# SelfTestWiring.net
KiCad netlist of a schematic drawn in EAGLE
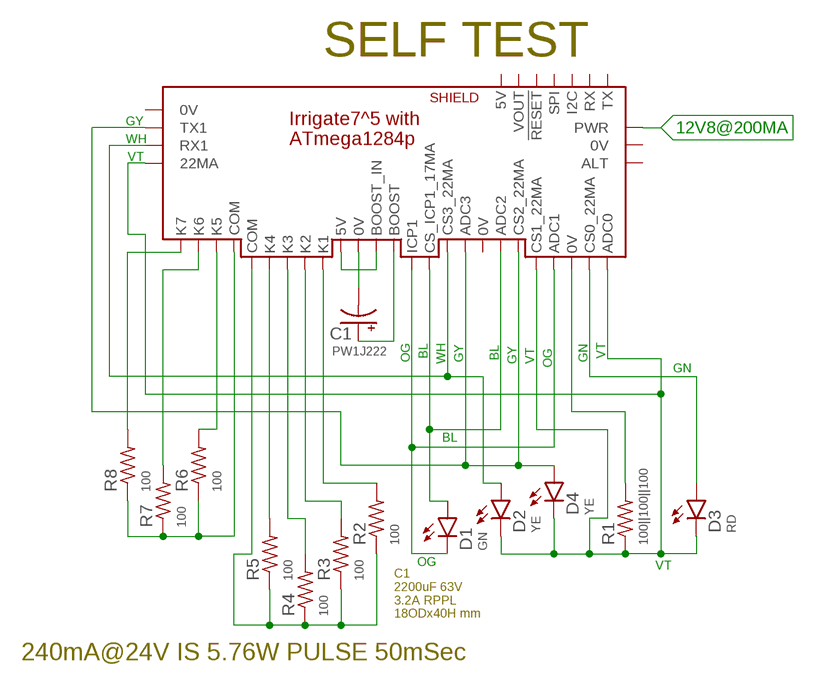
[diagram p0: schematic, sheet 1]

(export (version "E")
  (design (tool "Eeschema 10.0.6"))
  (components
    (comp (ref "C1")
      (value "PW1J222")
      (footprint "eagle-import:E7,5-18")
      (libsource (lib "eagle-import") (part "C-AL7.5X18"))
    )
    (comp (ref "D1")
      (value "GN")
      (footprint "eagle-import:LED5MM")
      (libsource (lib "eagle-import") (part "LED5MM"))
    )
    (comp (ref "D2")
      (value "YE")
      (footprint "eagle-import:LED5MM")
      (libsource (lib "eagle-import") (part "LED5MM"))
    )
    (comp (ref "D3")
      (value "RD")
      (footprint "eagle-import:LED5MM")
      (libsource (lib "eagle-import") (part "LED5MM"))
    )
    (comp (ref "D4")
      (value "YE")
      (footprint "eagle-import:LED5MM")
      (libsource (lib "eagle-import") (part "LED5MM"))
    )
    (comp (ref "R1")
      (value "100||100||100")
      (footprint "eagle-import:C0805(2012)")
      (libsource (lib "eagle-import") (part "R0805"))
    )
    (comp (ref "R2")
      (value "100")
      (footprint "eagle-import:C0805(2012)")
      (libsource (lib "eagle-import") (part "R0805"))
    )
    (comp (ref "R3")
      (value "100")
      (footprint "eagle-import:C0805(2012)")
      (libsource (lib "eagle-import") (part "R0805"))
    )
    (comp (ref "R4")
      (value "100")
      (footprint "eagle-import:C0805(2012)")
      (libsource (lib "eagle-import") (part "R0805"))
    )
    (comp (ref "R5")
      (value "100")
      (footprint "eagle-import:C0805(2012)")
      (libsource (lib "eagle-import") (part "R0805"))
    )
    (comp (ref "R6")
      (value "100")
      (footprint "eagle-import:C0805(2012)")
      (libsource (lib "eagle-import") (part "R0805"))
    )
    (comp (ref "R7")
      (value "100")
      (footprint "eagle-import:C0805(2012)")
      (libsource (lib "eagle-import") (part "R0805"))
    )
    (comp (ref "R8")
      (value "100")
      (footprint "eagle-import:C0805(2012)")
      (libsource (lib "eagle-import") (part "R0805"))
    )
    (comp (ref "U$2")
      (value "IRRIGATE7")
      (footprint "eagle-import:WITH_RPU_NAMES")
      (libsource (lib "eagle-import") (part "IRRIGATE7"))
    )
  )
  (nets
    (net (code "1") (name "/BL") (class "Default")
      (node (ref "D1") (pin "A") (pinfunction "A_A") (pintype "passive"))
      (node (ref "U$2") (pin "17MA@ICP1") (pinfunction "CS_ICP1_17MA_17MA@ICP1") (pintype "bidirectional"))
      (node (ref "U$2") (pin "ADC4") (pinfunction "ADC2_ADC4") (pintype "bidirectional"))
    )
    (net (code "2") (name "/GN") (class "Default")
      (node (ref "D3") (pin "A") (pinfunction "A_A") (pintype "passive"))
      (node (ref "U$2") (pin "22MA@ADC0") (pinfunction "CS0_22MA_22MA@ADC0") (pintype "bidirectional"))
    )
    (net (code "3") (name "/GY") (class "Default")
      (node (ref "D4") (pin "A") (pinfunction "A_A") (pintype "passive"))
      (node (ref "U$2") (pin "22MA@ADC4") (pinfunction "CS2_22MA_22MA@ADC4") (pintype "bidirectional"))
      (node (ref "U$2") (pin "ADC5") (pinfunction "ADC3_ADC5") (pintype "bidirectional"))
      (node (ref "U$2") (pin "DIO3") (pinfunction "TX1_DIO3") (pintype "bidirectional"))
    )
    (net (code "4") (name "/OG") (class "Default")
      (node (ref "D1") (pin "K") (pinfunction "K_K") (pintype "passive"))
      (node (ref "U$2") (pin "ADC1") (pinfunction "ADC1_ADC1") (pintype "bidirectional"))
      (node (ref "U$2") (pin "ICP1") (pinfunction "ICP1_ICP1") (pintype "bidirectional"))
    )
    (net (code "5") (name "/VT") (class "Default")
      (node (ref "D2") (pin "K") (pinfunction "K_K") (pintype "passive"))
      (node (ref "D3") (pin "K") (pinfunction "K_K") (pintype "passive"))
      (node (ref "D4") (pin "K") (pinfunction "K_K") (pintype "passive"))
      (node (ref "R1") (pin "1") (pinfunction "1_1") (pintype "passive"))
      (node (ref "U$2") (pin "22MA@ADC1") (pinfunction "CS1_22MA_22MA@ADC1") (pintype "bidirectional"))
      (node (ref "U$2") (pin "22MA@DIO2") (pinfunction "22MA_22MA@DIO2") (pintype "bidirectional"))
      (node (ref "U$2") (pin "ADC0") (pinfunction "ADC0_ADC0") (pintype "bidirectional"))
    )
    (net (code "6") (name "/WH") (class "Default")
      (node (ref "D2") (pin "A") (pinfunction "A_A") (pintype "passive"))
      (node (ref "U$2") (pin "22MA@ADC5") (pinfunction "CS3_22MA_22MA@ADC5") (pintype "bidirectional"))
      (node (ref "U$2") (pin "DIO2") (pinfunction "RX1_DIO2") (pintype "bidirectional"))
    )
    (net (code "7") (name "12V8@200MA") (class "Default")
      (node (ref "U$2") (pin "PWR") (pinfunction "PWR_PWR") (pintype "bidirectional"))
    )
    (net (code "8") (name "Net-(C1-Pad+)") (class "Default")
      (node (ref "C1") (pin "+") (pinfunction "+_+") (pintype "passive"))
      (node (ref "U$2") (pin "BOOST") (pinfunction "BOOST_BOOST") (pintype "bidirectional"))
    )
    (net (code "9") (name "Net-(C1-Pad-)") (class "Default")
      (node (ref "C1") (pin "-") (pinfunction "-_-") (pintype "passive"))
      (node (ref "U$2") (pin "0V") (pinfunction "0V_0V") (pintype "bidirectional"))
    )
    (net (code "10") (name "Net-(R1-Pad2)") (class "Default")
      (node (ref "R1") (pin "2") (pinfunction "2_2") (pintype "passive"))
      (node (ref "U$2") (pin "0V@ADC2") (pinfunction "0V_0V@ADC2") (pintype "bidirectional"))
    )
    (net (code "11") (name "Net-(R2-Pad1)") (class "Default")
      (node (ref "R2") (pin "1") (pinfunction "1_1") (pintype "passive"))
      (node (ref "R3") (pin "1") (pinfunction "1_1") (pintype "passive"))
      (node (ref "R4") (pin "1") (pinfunction "1_1") (pintype "passive"))
      (node (ref "R5") (pin "1") (pinfunction "1_1") (pintype "passive"))
      (node (ref "U$2") (pin "COM@K4") (pinfunction "COM_COM@K4") (pintype "bidirectional"))
    )
    (net (code "12") (name "Net-(R2-Pad2)") (class "Default")
      (node (ref "R2") (pin "2") (pinfunction "2_2") (pintype "passive"))
      (node (ref "U$2") (pin "K1") (pinfunction "K1_K1") (pintype "bidirectional"))
    )
    (net (code "13") (name "Net-(R3-Pad2)") (class "Default")
      (node (ref "R3") (pin "2") (pinfunction "2_2") (pintype "passive"))
      (node (ref "U$2") (pin "K2") (pinfunction "K2_K2") (pintype "bidirectional"))
    )
    (net (code "14") (name "Net-(R4-Pad2)") (class "Default")
      (node (ref "R4") (pin "2") (pinfunction "2_2") (pintype "passive"))
      (node (ref "U$2") (pin "K3") (pinfunction "K3_K3") (pintype "bidirectional"))
    )
    (net (code "15") (name "Net-(R5-Pad2)") (class "Default")
      (node (ref "R5") (pin "2") (pinfunction "2_2") (pintype "passive"))
      (node (ref "U$2") (pin "K4") (pinfunction "K4_K4") (pintype "bidirectional"))
    )
    (net (code "16") (name "Net-(R6-Pad1)") (class "Default")
      (node (ref "R6") (pin "1") (pinfunction "1_1") (pintype "passive"))
      (node (ref "R7") (pin "1") (pinfunction "1_1") (pintype "passive"))
      (node (ref "R8") (pin "1") (pinfunction "1_1") (pintype "passive"))
      (node (ref "U$2") (pin "COM@K5") (pinfunction "COM_COM@K5") (pintype "bidirectional"))
    )
    (net (code "17") (name "Net-(R6-Pad2)") (class "Default")
      (node (ref "R6") (pin "2") (pinfunction "2_2") (pintype "passive"))
      (node (ref "U$2") (pin "K5") (pinfunction "K5_K5") (pintype "bidirectional"))
    )
    (net (code "18") (name "Net-(R7-Pad2)") (class "Default")
      (node (ref "R7") (pin "2") (pinfunction "2_2") (pintype "passive"))
      (node (ref "U$2") (pin "K6") (pinfunction "K6_K6") (pintype "bidirectional"))
    )
    (net (code "19") (name "Net-(R8-Pad2)") (class "Default")
      (node (ref "R8") (pin "2") (pinfunction "2_2") (pintype "passive"))
      (node (ref "U$2") (pin "K7") (pinfunction "K7_K7") (pintype "bidirectional"))
    )
    (net (code "20") (name "Net-(U$2-Pad5V)") (class "Default")
      (node (ref "U$2") (pin "5V") (pinfunction "5V_5V") (pintype "bidirectional"))
      (node (ref "U$2") (pin "BOOST_IN") (pinfunction "BOOST_IN_BOOST_IN") (pintype "bidirectional"))
    )
    (net (code "21") (name "unconnected-(U$2-0V-Pad0V@PWR)") (class "Default")
      (node (ref "U$2") (pin "0V@PWR") (pinfunction "0V_0V@PWR") (pintype "bidirectional"))
    )
    (net (code "22") (name "unconnected-(U$2-0V-Pad17MA@ICP3)") (class "Default")
      (node (ref "U$2") (pin "17MA@ICP3") (pinfunction "0V_17MA@ICP3") (pintype "bidirectional"))
    )
    (net (code "23") (name "unconnected-(U$2-0V-PadICP3)") (class "Default")
      (node (ref "U$2") (pin "ICP3") (pinfunction "0V_ICP3") (pintype "bidirectional"))
    )
    (net (code "24") (name "unconnected-(U$2-5V-PadSHLD_5V)") (class "Default")
      (node (ref "U$2") (pin "SHLD_5V") (pinfunction "5V_SHLD_5V") (pintype "bidirectional"))
    )
    (net (code "25") (name "unconnected-(U$2-ALT-PadAUX)") (class "Default")
      (node (ref "U$2") (pin "AUX") (pinfunction "ALT_AUX") (pintype "bidirectional"))
    )
    (net (code "26") (name "unconnected-(U$2-PadI2C)") (class "Default")
      (node (ref "U$2") (pin "I2C") (pinfunction "I2C_I2C") (pintype "bidirectional"))
    )
    (net (code "27") (name "unconnected-(U$2-PadRX)") (class "Default")
      (node (ref "U$2") (pin "RX") (pinfunction "RX_RX") (pintype "bidirectional"))
    )
    (net (code "28") (name "unconnected-(U$2-PadSPI)") (class "Default")
      (node (ref "U$2") (pin "SPI") (pinfunction "SPI_SPI") (pintype "bidirectional"))
    )
    (net (code "29") (name "unconnected-(U$2-PadTX)") (class "Default")
      (node (ref "U$2") (pin "TX") (pinfunction "TX_TX") (pintype "bidirectional"))
    )
    (net (code "30") (name "unconnected-(U$2-VOUT-PadSHLD_VOUT)") (class "Default")
      (node (ref "U$2") (pin "SHLD_VOUT") (pinfunction "VOUT_SHLD_VOUT") (pintype "bidirectional"))
    )
    (net (code "31") (name "unconnected-(U$2-~{RESET}-Pad!RESET)") (class "Default")
      (node (ref "U$2") (pin "!RESET") (pinfunction "~{RESET}_!RESET") (pintype "bidirectional"))
    )
  )
)
